# design.net
KiCad netlist of a schematic drawn in Altium Designer
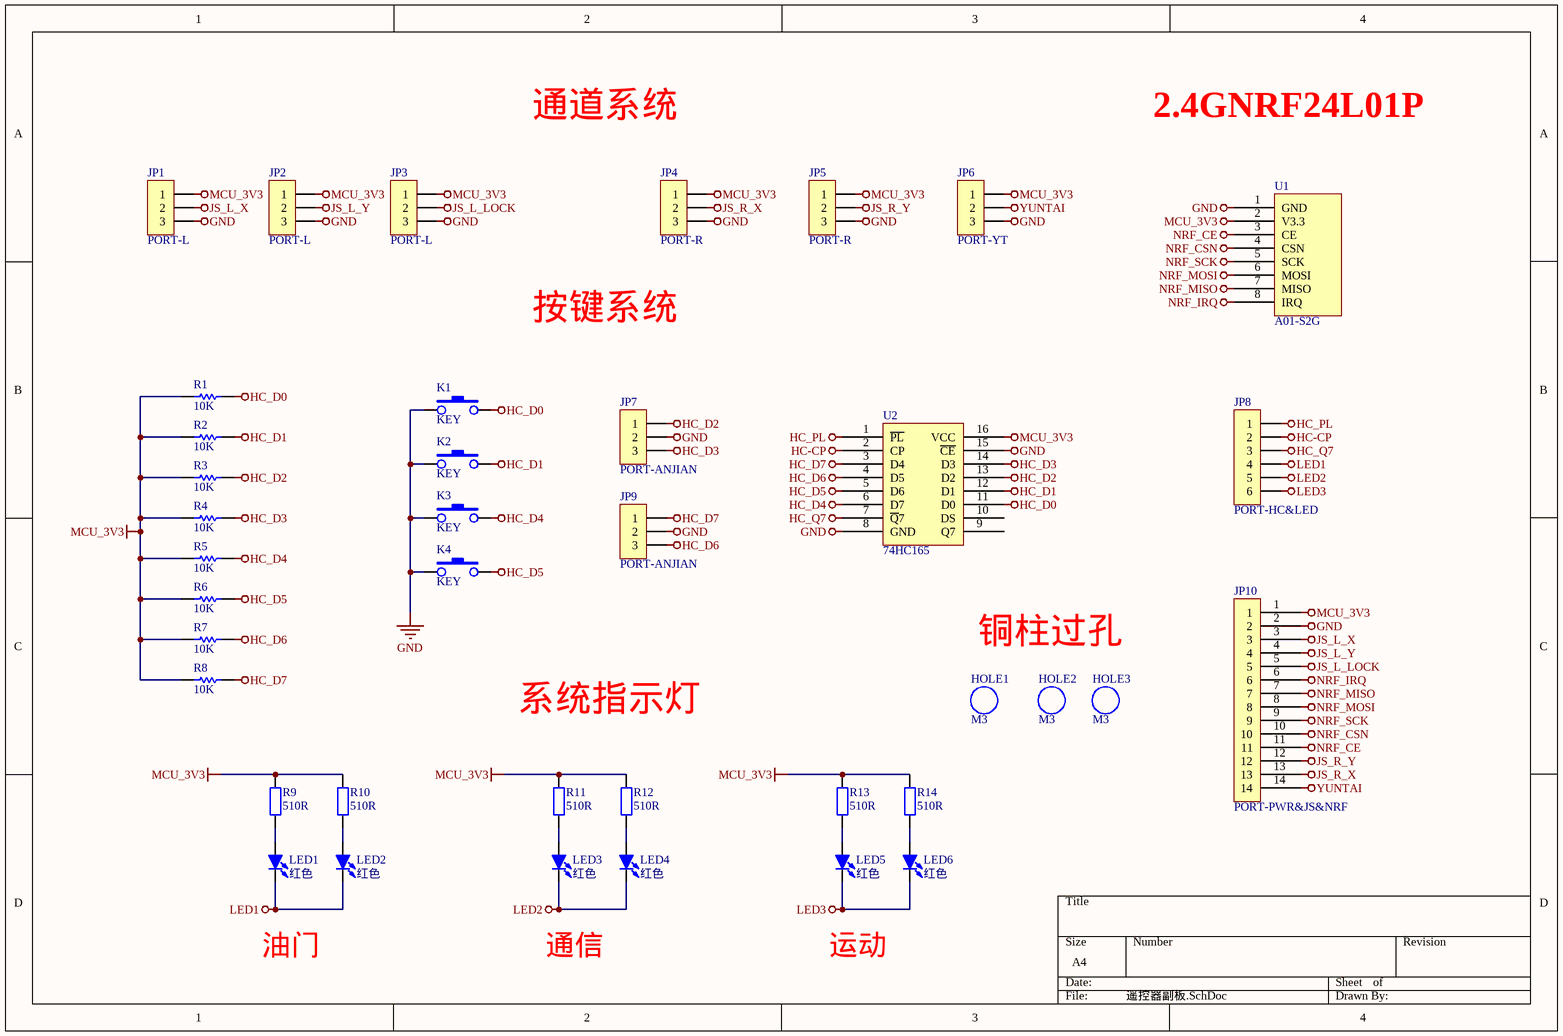
[diagram p0: 遥控器副板.SchDoc]

(export (version "E")
  (design (tool "Eeschema 10.0.6"))
  (components
    (comp (ref "HOLE1")
      (value "M3")
      (footprint "M3 5.4MM")
      (description "铜柱孔")
      (fields (field (name "版权归属") "源创客"))
      (libsource (lib "STM32F407_CORE_BOARD") (part "M3"))
    )
    (comp (ref "HOLE2")
      (value "M3")
      (footprint "M3 5.4MM")
      (description "铜柱孔")
      (fields (field (name "版权归属") "源创客"))
      (libsource (lib "STM32F407_CORE_BOARD") (part "M3"))
    )
    (comp (ref "HOLE3")
      (value "M3")
      (footprint "M3 5.4MM")
      (description "铜柱孔")
      (fields (field (name "版权归属") "源创客"))
      (libsource (lib "STM32F407_CORE_BOARD") (part "M3"))
    )
    (comp (ref "JP1")
      (value "PORT-L")
      (footprint "MX 1.25-WS-3P")
      (description "3P接插件")
      (fields (field (name "版权归属") "源创客"))
      (libsource (lib "ATKF405 V1.1") (part "Header 3"))
    )
    (comp (ref "JP2")
      (value "PORT-L")
      (footprint "MX 1.25-WS-3P")
      (description "3P接插件")
      (fields (field (name "版权归属") "源创客"))
      (libsource (lib "ATKF405 V1.1") (part "Header 3"))
    )
    (comp (ref "JP3")
      (value "PORT-L")
      (footprint "MX 1.25-WS-3P")
      (description "3P接插件")
      (fields (field (name "版权归属") "源创客"))
      (libsource (lib "ATKF405 V1.1") (part "Header 3"))
    )
    (comp (ref "JP4")
      (value "PORT-R")
      (footprint "MX 1.25-WS-3P")
      (description "3P接插件")
      (fields (field (name "版权归属") "源创客"))
      (libsource (lib "ATKF405 V1.1") (part "Header 3"))
    )
    (comp (ref "JP5")
      (value "PORT-R")
      (footprint "MX 1.25-WS-3P")
      (description "3P接插件")
      (fields (field (name "版权归属") "源创客"))
      (libsource (lib "ATKF405 V1.1") (part "Header 3"))
    )
    (comp (ref "JP6")
      (value "PORT-YT")
      (footprint "MX 1.25-WS-3P")
      (description "3P接插件")
      (fields (field (name "版权归属") "源创客"))
      (libsource (lib "ATKF405 V1.1") (part "Header 3"))
    )
    (comp (ref "JP7")
      (value "PORT-ANJIAN")
      (footprint "MX 1.25-WS-3P")
      (description "3P接插件")
      (fields (field (name "版权归属") "源创客"))
      (libsource (lib "ATKF405 V1.1") (part "Header 3"))
    )
    (comp (ref "JP8")
      (value "PORT-HC&LED")
      (footprint "SH1.0 S-W-6P")
      (description "6P接插件")
      (fields (field (name "版权归属") "源创客"))
      (libsource (lib "ATKF405 V1.1") (part "Header 6"))
    )
    (comp (ref "JP9")
      (value "PORT-ANJIAN")
      (footprint "MX 1.25-WS-3P")
      (description "3P接插件")
      (fields (field (name "版权归属") "源创客"))
      (libsource (lib "ATKF405 V1.1") (part "Header 3"))
    )
    (comp (ref "JP10")
      (value "PORT-PWR&JS&NRF")
      (footprint "Headr14")
      (description "卧贴 14PIN 1.25mm")
      (libsource (lib "遥控器主板") (part "HEADER 14"))
    )
    (comp (ref "K1") (value "KEY") (footprint "SMD-6X6X8") (libsource (lib "轻触开关") (part "KEY")))
    (comp (ref "K2") (value "KEY") (footprint "SMD-6X6X8") (libsource (lib "轻触开关") (part "KEY")))
    (comp (ref "K3") (value "KEY") (footprint "SMD-6X6X8") (libsource (lib "轻触开关") (part "KEY")))
    (comp (ref "K4") (value "KEY") (footprint "SMD-6X6X8") (libsource (lib "轻触开关") (part "KEY")))
    (comp (ref "LED1")
      (value "红色")
      (footprint "LED 0603R")
      (description "贴片LED")
      (fields (field (name "版权归属") "源创客"))
      (libsource (lib "STM32F407_CORE_BOARD") (part "LED-SMD"))
    )
    (comp (ref "LED2")
      (value "红色")
      (footprint "LED 0603R")
      (description "贴片LED")
      (fields (field (name "版权归属") "源创客"))
      (libsource (lib "STM32F407_CORE_BOARD") (part "LED-SMD"))
    )
    (comp (ref "LED3")
      (value "红色")
      (footprint "LED 0603R")
      (description "贴片LED")
      (fields (field (name "版权归属") "源创客"))
      (libsource (lib "STM32F407_CORE_BOARD") (part "LED-SMD"))
    )
    (comp (ref "LED4")
      (value "红色")
      (footprint "LED 0603R")
      (description "贴片LED")
      (fields (field (name "版权归属") "源创客"))
      (libsource (lib "STM32F407_CORE_BOARD") (part "LED-SMD"))
    )
    (comp (ref "LED5")
      (value "红色")
      (footprint "LED 0603R")
      (description "贴片LED")
      (fields (field (name "版权归属") "源创客"))
      (libsource (lib "STM32F407_CORE_BOARD") (part "LED-SMD"))
    )
    (comp (ref "LED6")
      (value "红色")
      (footprint "LED 0603R")
      (description "贴片LED")
      (fields (field (name "版权归属") "源创客"))
      (libsource (lib "STM32F407_CORE_BOARD") (part "LED-SMD"))
    )
    (comp (ref "R1") (value "10K") (footprint "0805R") (libsource (lib "电阻") (part "RES")))
    (comp (ref "R2") (value "10K") (footprint "0805R") (libsource (lib "电阻") (part "RES")))
    (comp (ref "R3") (value "10K") (footprint "0805R") (libsource (lib "电阻") (part "RES")))
    (comp (ref "R4") (value "10K") (footprint "0805R") (libsource (lib "电阻") (part "RES")))
    (comp (ref "R5") (value "10K") (footprint "0805R") (libsource (lib "电阻") (part "RES")))
    (comp (ref "R6") (value "10K") (footprint "0805R") (libsource (lib "电阻") (part "RES")))
    (comp (ref "R7") (value "10K") (footprint "0805R") (libsource (lib "电阻") (part "RES")))
    (comp (ref "R8") (value "10K") (footprint "0805R") (libsource (lib "电阻") (part "RES")))
    (comp (ref "R9")
      (value "510R")
      (footprint "0805R")
      (description "贴片电阻")
      (fields (field (name "版权归属") "源创客"))
      (libsource (lib "STM32F407_CORE_BOARD") (part "R"))
    )
    (comp (ref "R10")
      (value "510R")
      (footprint "0805R")
      (description "贴片电阻")
      (fields (field (name "版权归属") "源创客"))
      (libsource (lib "STM32F407_CORE_BOARD") (part "R"))
    )
    (comp (ref "R11")
      (value "510R")
      (footprint "0805R")
      (description "贴片电阻")
      (fields (field (name "版权归属") "源创客"))
      (libsource (lib "STM32F407_CORE_BOARD") (part "R"))
    )
    (comp (ref "R12")
      (value "510R")
      (footprint "0805R")
      (description "贴片电阻")
      (fields (field (name "版权归属") "源创客"))
      (libsource (lib "STM32F407_CORE_BOARD") (part "R"))
    )
    (comp (ref "R13")
      (value "510R")
      (footprint "0805R")
      (description "贴片电阻")
      (fields (field (name "版权归属") "源创客"))
      (libsource (lib "STM32F407_CORE_BOARD") (part "R"))
    )
    (comp (ref "R14")
      (value "510R")
      (footprint "0805R")
      (description "贴片电阻")
      (fields (field (name "版权归属") "源创客"))
      (libsource (lib "STM32F407_CORE_BOARD") (part "R"))
    )
    (comp (ref "U1") (value "A01-S2G") (footprint "A01-S2G") (libsource (lib "遥控器副板") (part "A01-S2G")))
    (comp (ref "U2") (value "74HC165") (footprint "SOP16") (libsource (lib "遥控器副板") (part "74HC165")))
  )
  (nets
    (net (code "1") (name "GND") (class "Default")
      (node (ref "JP1") (pin "3") (pinfunction "3_3") (pintype "passive"))
      (node (ref "JP10") (pin "2") (pinfunction "2_2") (pintype "passive"))
      (node (ref "JP2") (pin "3") (pinfunction "3_3") (pintype "passive"))
      (node (ref "JP3") (pin "3") (pinfunction "3_3") (pintype "passive"))
      (node (ref "JP4") (pin "3") (pinfunction "3_3") (pintype "passive"))
      (node (ref "JP5") (pin "3") (pinfunction "3_3") (pintype "passive"))
      (node (ref "JP6") (pin "3") (pinfunction "3_3") (pintype "passive"))
      (node (ref "JP7") (pin "2") (pinfunction "2_2") (pintype "passive"))
      (node (ref "JP9") (pin "2") (pinfunction "2_2") (pintype "passive"))
      (node (ref "K1") (pin "1") (pinfunction "1_1") (pintype "passive"))
      (node (ref "K2") (pin "1") (pinfunction "1_1") (pintype "passive"))
      (node (ref "K3") (pin "1") (pinfunction "1_1") (pintype "passive"))
      (node (ref "K4") (pin "1") (pinfunction "1_1") (pintype "passive"))
      (node (ref "U1") (pin "1") (pinfunction "GND_1") (pintype "passive"))
      (node (ref "U2") (pin "15") (pinfunction "~{CE}_15") (pintype "passive"))
      (node (ref "U2") (pin "8") (pinfunction "GND_8") (pintype "passive"))
    )
    (net (code "2") (name "HC-CP") (class "Default")
      (node (ref "JP8") (pin "2") (pinfunction "2_2") (pintype "passive"))
      (node (ref "U2") (pin "2") (pinfunction "CP_2") (pintype "passive"))
    )
    (net (code "3") (name "HC_D0") (class "Default")
      (node (ref "K1") (pin "3") (pinfunction "3_3") (pintype "passive"))
      (node (ref "R1") (pin "2") (pinfunction "2_2") (pintype "passive"))
      (node (ref "U2") (pin "11") (pinfunction "D0_11") (pintype "passive"))
    )
    (net (code "4") (name "HC_D1") (class "Default")
      (node (ref "K2") (pin "3") (pinfunction "3_3") (pintype "passive"))
      (node (ref "R2") (pin "2") (pinfunction "2_2") (pintype "passive"))
      (node (ref "U2") (pin "12") (pinfunction "D1_12") (pintype "passive"))
    )
    (net (code "5") (name "HC_D2") (class "Default")
      (node (ref "JP7") (pin "1") (pinfunction "1_1") (pintype "passive"))
      (node (ref "R3") (pin "2") (pinfunction "2_2") (pintype "passive"))
      (node (ref "U2") (pin "13") (pinfunction "D2_13") (pintype "passive"))
    )
    (net (code "6") (name "HC_D3") (class "Default")
      (node (ref "JP7") (pin "3") (pinfunction "3_3") (pintype "passive"))
      (node (ref "R4") (pin "2") (pinfunction "2_2") (pintype "passive"))
      (node (ref "U2") (pin "14") (pinfunction "D3_14") (pintype "passive"))
    )
    (net (code "7") (name "HC_D4") (class "Default")
      (node (ref "K3") (pin "3") (pinfunction "3_3") (pintype "passive"))
      (node (ref "R5") (pin "2") (pinfunction "2_2") (pintype "passive"))
      (node (ref "U2") (pin "6") (pinfunction "D7_6") (pintype "passive"))
    )
    (net (code "8") (name "HC_D5") (class "Default")
      (node (ref "K4") (pin "3") (pinfunction "3_3") (pintype "passive"))
      (node (ref "R6") (pin "2") (pinfunction "2_2") (pintype "passive"))
      (node (ref "U2") (pin "5") (pinfunction "D6_5") (pintype "passive"))
    )
    (net (code "9") (name "HC_D6") (class "Default")
      (node (ref "JP9") (pin "3") (pinfunction "3_3") (pintype "passive"))
      (node (ref "R7") (pin "2") (pinfunction "2_2") (pintype "passive"))
      (node (ref "U2") (pin "4") (pinfunction "D5_4") (pintype "passive"))
    )
    (net (code "10") (name "HC_D7") (class "Default")
      (node (ref "JP9") (pin "1") (pinfunction "1_1") (pintype "passive"))
      (node (ref "R8") (pin "2") (pinfunction "2_2") (pintype "passive"))
      (node (ref "U2") (pin "3") (pinfunction "D4_3") (pintype "passive"))
    )
    (net (code "11") (name "HC_PL") (class "Default")
      (node (ref "JP8") (pin "1") (pinfunction "1_1") (pintype "passive"))
      (node (ref "U2") (pin "1") (pinfunction "~{PL}_1") (pintype "passive"))
    )
    (net (code "12") (name "HC_Q7") (class "Default")
      (node (ref "JP8") (pin "3") (pinfunction "3_3") (pintype "passive"))
      (node (ref "U2") (pin "7") (pinfunction "~{Q}7_7") (pintype "passive"))
    )
    (net (code "13") (name "JS_L_LOCK") (class "Default")
      (node (ref "JP10") (pin "5") (pinfunction "5_5") (pintype "passive"))
      (node (ref "JP3") (pin "2") (pinfunction "2_2") (pintype "passive"))
    )
    (net (code "14") (name "JS_L_X") (class "Default")
      (node (ref "JP1") (pin "2") (pinfunction "2_2") (pintype "passive"))
      (node (ref "JP10") (pin "3") (pinfunction "3_3") (pintype "passive"))
    )
    (net (code "15") (name "JS_L_Y") (class "Default")
      (node (ref "JP10") (pin "4") (pinfunction "4_4") (pintype "passive"))
      (node (ref "JP2") (pin "2") (pinfunction "2_2") (pintype "passive"))
    )
    (net (code "16") (name "JS_R_X") (class "Default")
      (node (ref "JP10") (pin "13") (pinfunction "13_13") (pintype "passive"))
      (node (ref "JP4") (pin "2") (pinfunction "2_2") (pintype "passive"))
    )
    (net (code "17") (name "JS_R_Y") (class "Default")
      (node (ref "JP10") (pin "12") (pinfunction "12_12") (pintype "passive"))
      (node (ref "JP5") (pin "2") (pinfunction "2_2") (pintype "passive"))
    )
    (net (code "18") (name "LED1") (class "Default")
      (node (ref "JP8") (pin "4") (pinfunction "4_4") (pintype "passive"))
      (node (ref "LED1") (pin "2") (pinfunction "K_2") (pintype "passive"))
      (node (ref "LED2") (pin "2") (pinfunction "K_2") (pintype "passive"))
    )
    (net (code "19") (name "LED2") (class "Default")
      (node (ref "JP8") (pin "5") (pinfunction "5_5") (pintype "passive"))
      (node (ref "LED3") (pin "2") (pinfunction "K_2") (pintype "passive"))
      (node (ref "LED4") (pin "2") (pinfunction "K_2") (pintype "passive"))
    )
    (net (code "20") (name "LED3") (class "Default")
      (node (ref "JP8") (pin "6") (pinfunction "6_6") (pintype "passive"))
      (node (ref "LED5") (pin "2") (pinfunction "K_2") (pintype "passive"))
      (node (ref "LED6") (pin "2") (pinfunction "K_2") (pintype "passive"))
    )
    (net (code "21") (name "MCU_3V3") (class "Default")
      (node (ref "JP1") (pin "1") (pinfunction "1_1") (pintype "passive"))
      (node (ref "JP10") (pin "1") (pinfunction "1_1") (pintype "passive"))
      (node (ref "JP2") (pin "1") (pinfunction "1_1") (pintype "passive"))
      (node (ref "JP3") (pin "1") (pinfunction "1_1") (pintype "passive"))
      (node (ref "JP4") (pin "1") (pinfunction "1_1") (pintype "passive"))
      (node (ref "JP5") (pin "1") (pinfunction "1_1") (pintype "passive"))
      (node (ref "JP6") (pin "1") (pinfunction "1_1") (pintype "passive"))
      (node (ref "R1") (pin "1") (pinfunction "1_1") (pintype "passive"))
      (node (ref "R10") (pin "2") (pinfunction "2_2") (pintype "passive"))
      (node (ref "R11") (pin "2") (pinfunction "2_2") (pintype "passive"))
      (node (ref "R12") (pin "2") (pinfunction "2_2") (pintype "passive"))
      (node (ref "R13") (pin "2") (pinfunction "2_2") (pintype "passive"))
      (node (ref "R14") (pin "2") (pinfunction "2_2") (pintype "passive"))
      (node (ref "R2") (pin "1") (pinfunction "1_1") (pintype "passive"))
      (node (ref "R3") (pin "1") (pinfunction "1_1") (pintype "passive"))
      (node (ref "R4") (pin "1") (pinfunction "1_1") (pintype "passive"))
      (node (ref "R5") (pin "1") (pinfunction "1_1") (pintype "passive"))
      (node (ref "R6") (pin "1") (pinfunction "1_1") (pintype "passive"))
      (node (ref "R7") (pin "1") (pinfunction "1_1") (pintype "passive"))
      (node (ref "R8") (pin "1") (pinfunction "1_1") (pintype "passive"))
      (node (ref "R9") (pin "2") (pinfunction "2_2") (pintype "passive"))
      (node (ref "U1") (pin "2") (pinfunction "V3.3_2") (pintype "passive"))
      (node (ref "U2") (pin "16") (pinfunction "VCC_16") (pintype "passive"))
    )
    (net (code "22") (name "NRF_CE") (class "Default")
      (node (ref "JP10") (pin "11") (pinfunction "11_11") (pintype "passive"))
      (node (ref "U1") (pin "3") (pinfunction "CE_3") (pintype "passive"))
    )
    (net (code "23") (name "NRF_CSN") (class "Default")
      (node (ref "JP10") (pin "10") (pinfunction "10_10") (pintype "passive"))
      (node (ref "U1") (pin "4") (pinfunction "CSN_4") (pintype "passive"))
    )
    (net (code "24") (name "NRF_IRQ") (class "Default")
      (node (ref "JP10") (pin "6") (pinfunction "6_6") (pintype "passive"))
      (node (ref "U1") (pin "8") (pinfunction "IRQ_8") (pintype "passive"))
    )
    (net (code "25") (name "NRF_MISO") (class "Default")
      (node (ref "JP10") (pin "7") (pinfunction "7_7") (pintype "passive"))
      (node (ref "U1") (pin "7") (pinfunction "MISO_7") (pintype "passive"))
    )
    (net (code "26") (name "NRF_MOSI") (class "Default")
      (node (ref "JP10") (pin "8") (pinfunction "8_8") (pintype "passive"))
      (node (ref "U1") (pin "6") (pinfunction "MOSI_6") (pintype "passive"))
    )
    (net (code "27") (name "NRF_SCK") (class "Default")
      (node (ref "JP10") (pin "9") (pinfunction "9_9") (pintype "passive"))
      (node (ref "U1") (pin "5") (pinfunction "SCK_5") (pintype "passive"))
    )
    (net (code "28") (name "Net-(LED1-A)") (class "Default")
      (node (ref "LED1") (pin "1") (pinfunction "A_1") (pintype "passive"))
      (node (ref "R9") (pin "1") (pinfunction "1_1") (pintype "passive"))
    )
    (net (code "29") (name "Net-(LED2-A)") (class "Default")
      (node (ref "LED2") (pin "1") (pinfunction "A_1") (pintype "passive"))
      (node (ref "R10") (pin "1") (pinfunction "1_1") (pintype "passive"))
    )
    (net (code "30") (name "Net-(LED3-A)") (class "Default")
      (node (ref "LED3") (pin "1") (pinfunction "A_1") (pintype "passive"))
      (node (ref "R11") (pin "1") (pinfunction "1_1") (pintype "passive"))
    )
    (net (code "31") (name "Net-(LED4-A)") (class "Default")
      (node (ref "LED4") (pin "1") (pinfunction "A_1") (pintype "passive"))
      (node (ref "R12") (pin "1") (pinfunction "1_1") (pintype "passive"))
    )
    (net (code "32") (name "Net-(LED5-A)") (class "Default")
      (node (ref "LED5") (pin "1") (pinfunction "A_1") (pintype "passive"))
      (node (ref "R13") (pin "1") (pinfunction "1_1") (pintype "passive"))
    )
    (net (code "33") (name "Net-(LED6-A)") (class "Default")
      (node (ref "LED6") (pin "1") (pinfunction "A_1") (pintype "passive"))
      (node (ref "R14") (pin "1") (pinfunction "1_1") (pintype "passive"))
    )
    (net (code "34") (name "YUNTAI") (class "Default")
      (node (ref "JP10") (pin "14") (pinfunction "14_14") (pintype "passive"))
      (node (ref "JP6") (pin "2") (pinfunction "2_2") (pintype "passive"))
    )
    (net (code "35") (name "unconnected-(U2-DS-Pad10)") (class "Default")
      (node (ref "U2") (pin "10") (pinfunction "DS_10") (pintype "passive"))
    )
    (net (code "36") (name "unconnected-(U2-Q7-Pad9)") (class "Default")
      (node (ref "U2") (pin "9") (pinfunction "Q7_9") (pintype "passive"))
    )
  )
)
